# jcbp-290.net
KiCad netlist of a schematic drawn in EAGLE
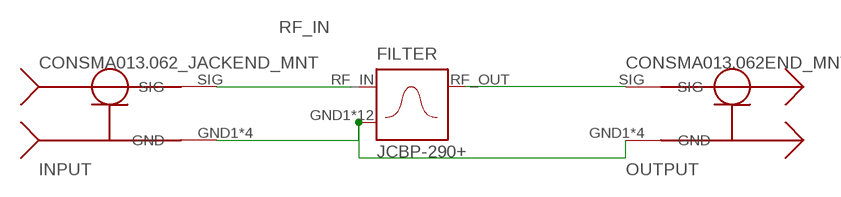
[diagram p0: schematic, sheet 1]

(export (version "E")
  (design (tool "Eeschema 10.0.6"))
  (components
    (comp (ref "FILTER")
      (value "JCBP-290+")
      (footprint "eagle-import:BG291")
      (libsource (lib "eagle-import") (part "JCBP-290+"))
    )
    (comp (ref "INPUT")
      (value "CONSMA013.062_JACKEND_MNT")
      (footprint "eagle-import:SMA_EDGE_MNT")
      (libsource (lib "eagle-import") (part "CONSMA013.062_JACKEND_MNT"))
    )
    (comp (ref "OUTPUT")
      (value "CONSMA013.062END_MNT")
      (footprint "eagle-import:SMA_EDGE_MNT")
      (libsource (lib "eagle-import") (part "CONSMA013.062END_MNT"))
    )
  )
  (nets
    (net (code "1") (name "/RF_IN") (class "Default")
      (node (ref "FILTER") (pin "RF_IN") (pinfunction "RF_IN_RF_IN") (pintype "input"))
      (node (ref "INPUT") (pin "SIG") (pinfunction "SIG_SIG") (pintype "bidirectional"))
    )
    (net (code "2") (name "Net-(FILTER-GND-PadGND1)") (class "Default")
      (node (ref "FILTER") (pin "GND1") (pinfunction "GND_GND1") (pintype "bidirectional"))
      (node (ref "FILTER") (pin "GND10") (pinfunction "GND_GND10") (pintype "bidirectional"))
      (node (ref "FILTER") (pin "GND11") (pinfunction "GND_GND11") (pintype "bidirectional"))
      (node (ref "FILTER") (pin "GND12") (pinfunction "GND_GND12") (pintype "bidirectional"))
      (node (ref "FILTER") (pin "GND13") (pinfunction "GND_GND13") (pintype "bidirectional"))
      (node (ref "FILTER") (pin "GND14") (pinfunction "GND_GND14") (pintype "bidirectional"))
      (node (ref "FILTER") (pin "GND3") (pinfunction "GND_GND3") (pintype "bidirectional"))
      (node (ref "FILTER") (pin "GND4") (pinfunction "GND_GND4") (pintype "bidirectional"))
      (node (ref "FILTER") (pin "GND5") (pinfunction "GND_GND5") (pintype "bidirectional"))
      (node (ref "FILTER") (pin "GND6") (pinfunction "GND_GND6") (pintype "bidirectional"))
      (node (ref "FILTER") (pin "GND7") (pinfunction "GND_GND7") (pintype "bidirectional"))
      (node (ref "FILTER") (pin "GND8") (pinfunction "GND_GND8") (pintype "bidirectional"))
      (node (ref "INPUT") (pin "GND1") (pinfunction "GND_GND1") (pintype "bidirectional"))
      (node (ref "INPUT") (pin "GND2") (pinfunction "GND_GND2") (pintype "bidirectional"))
      (node (ref "INPUT") (pin "GND3") (pinfunction "GND_GND3") (pintype "bidirectional"))
      (node (ref "INPUT") (pin "GND4") (pinfunction "GND_GND4") (pintype "bidirectional"))
      (node (ref "OUTPUT") (pin "GND1") (pinfunction "GND_GND1") (pintype "bidirectional"))
      (node (ref "OUTPUT") (pin "GND2") (pinfunction "GND_GND2") (pintype "bidirectional"))
      (node (ref "OUTPUT") (pin "GND3") (pinfunction "GND_GND3") (pintype "bidirectional"))
      (node (ref "OUTPUT") (pin "GND4") (pinfunction "GND_GND4") (pintype "bidirectional"))
    )
    (net (code "3") (name "Net-(FILTER-PadRF_OUT)") (class "Default")
      (node (ref "FILTER") (pin "RF_OUT") (pinfunction "RF_OUT_RF_OUT") (pintype "output"))
      (node (ref "OUTPUT") (pin "SIG") (pinfunction "SIG_SIG") (pintype "bidirectional"))
    )
  )
)
